# Drive_21_04_33.net
KiCad netlist of a schematic drawn in Altium Designer
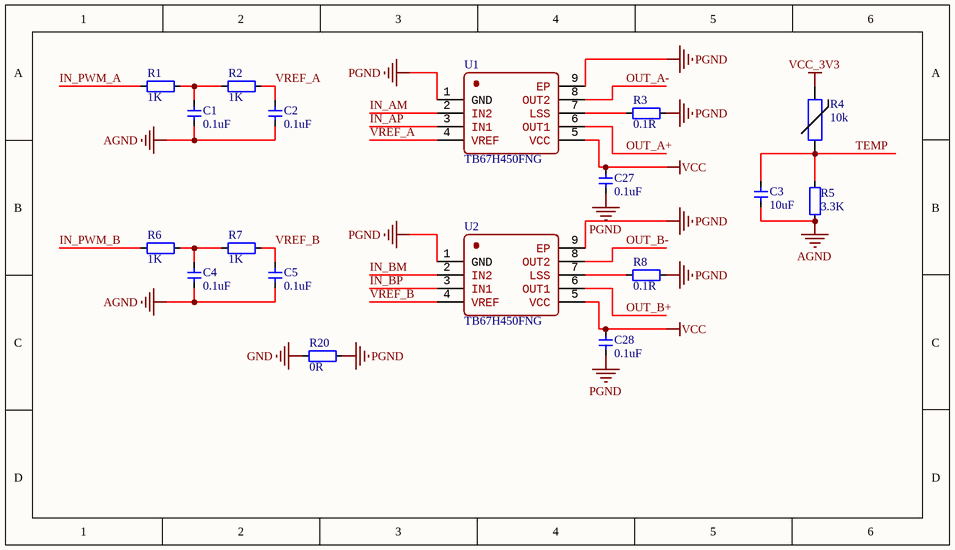
[diagram p0: Drive 21.04.33.SchDoc]

(export (version "E")
  (design (tool "Eeschema 10.0.6"))
  (components
    (comp (ref "C1")
      (value "0.1uF")
      (footprint "motor42-lib:CAP_0402")
      (description "Capacitor")
      (libsource (lib "MyPcbLib") (part "电容-0402"))
    )
    (comp (ref "C2")
      (value "0.1uF")
      (footprint "motor42-lib:CAP_0402")
      (description "Capacitor")
      (libsource (lib "MyPcbLib") (part "电容-0402"))
    )
    (comp (ref "C3")
      (value "10uF")
      (footprint "CAP_0402")
      (description "Capacitor")
      (libsource (lib "MyPcbLib") (part "电容-0402"))
    )
    (comp (ref "C4")
      (value "0.1uF")
      (footprint "motor42-lib:CAP_0402")
      (description "Capacitor")
      (libsource (lib "MyPcbLib") (part "电容-0402"))
    )
    (comp (ref "C5")
      (value "0.1uF")
      (footprint "motor42-lib:CAP_0402")
      (description "Capacitor")
      (libsource (lib "MyPcbLib") (part "电容-0402"))
    )
    (comp (ref "C27")
      (value "0.1uF")
      (footprint "motor42-lib:CAP_0402")
      (description "Capacitor")
      (libsource (lib "MyPcbLib") (part "电容-0402"))
    )
    (comp (ref "C28")
      (value "0.1uF")
      (footprint "motor42-lib:CAP_0402")
      (description "Capacitor")
      (libsource (lib "MyPcbLib") (part "电容-0402"))
    )
    (comp (ref "R1")
      (value "1K")
      (footprint "RES_0402")
      (description "Resistor")
      (libsource (lib "MyPcbLib") (part "电阻-0402"))
    )
    (comp (ref "R2")
      (value "1K")
      (footprint "RES_0402")
      (description "Resistor")
      (libsource (lib "MyPcbLib") (part "电阻-0402"))
    )
    (comp (ref "R3")
      (value "0.1R")
      (footprint "1206-RES")
      (description "Resistor")
      (libsource (lib "MyPcbLib") (part "电阻-1206"))
    )
    (comp (ref "R4")
      (value "10k")
      (footprint "RES_0402")
      (description "THERMISTOR 10K OHM NTC 0402 SMD")
      (fields (field (name "Comment") "NCP15XH103F03RC"))
      (libsource (lib "MyPcbLib") (part "NCP15XH103F03RC"))
    )
    (comp (ref "R5")
      (value "3.3K")
      (footprint "RES_0402")
      (description "Resistor")
      (libsource (lib "") (part "电阻-0402_1"))
    )
    (comp (ref "R6")
      (value "1K")
      (footprint "RES_0402")
      (description "Resistor")
      (libsource (lib "MyPcbLib") (part "电阻-0402"))
    )
    (comp (ref "R7")
      (value "1K")
      (footprint "RES_0402")
      (description "Resistor")
      (libsource (lib "MyPcbLib") (part "电阻-0402"))
    )
    (comp (ref "R8")
      (value "0.1R")
      (footprint "1206-RES")
      (description "Resistor")
      (libsource (lib "MyPcbLib") (part "电阻-1206"))
    )
    (comp (ref "R20")
      (value "0R")
      (footprint "1206-RES")
      (description "Resistor")
      (libsource (lib "MyPcbLib") (part "电阻-1206"))
    )
    (comp (ref "U1")
      (value "TB67H450FNG")
      (footprint "SO-8-PAD")
      (description "PWM Chopper Type DC Brushed Motor Driver")
      (libsource (lib "MyPcbLib") (part "TB67H450FNG"))
    )
    (comp (ref "U2")
      (value "TB67H450FNG")
      (footprint "SO-8-PAD")
      (description "PWM Chopper Type DC Brushed Motor Driver")
      (libsource (lib "MyPcbLib") (part "TB67H450FNG"))
    )
  )
  (nets
    (net (code "1") (name "/IN_AM") (class "Default")
      (node (ref "U1") (pin "2") (pinfunction "IN2_2") (pintype "passive"))
    )
    (net (code "2") (name "/IN_AP") (class "Default")
      (node (ref "U1") (pin "3") (pinfunction "IN1_3") (pintype "passive"))
    )
    (net (code "3") (name "/IN_BM") (class "Default")
      (node (ref "U2") (pin "2") (pinfunction "IN2_2") (pintype "passive"))
    )
    (net (code "4") (name "/IN_BP") (class "Default")
      (node (ref "U2") (pin "3") (pinfunction "IN1_3") (pintype "passive"))
    )
    (net (code "5") (name "/IN_PWM_A") (class "Default")
      (node (ref "R1") (pin "1") (pinfunction "1_1") (pintype "passive"))
    )
    (net (code "6") (name "/IN_PWM_B") (class "Default")
      (node (ref "R6") (pin "1") (pinfunction "1_1") (pintype "passive"))
    )
    (net (code "7") (name "/OUT_A+") (class "Default")
      (node (ref "U1") (pin "6") (pinfunction "OUT1_6") (pintype "passive"))
    )
    (net (code "8") (name "/OUT_A-") (class "Default")
      (node (ref "U1") (pin "8") (pinfunction "OUT2_8") (pintype "passive"))
    )
    (net (code "9") (name "/OUT_B+") (class "Default")
      (node (ref "U2") (pin "6") (pinfunction "OUT1_6") (pintype "passive"))
    )
    (net (code "10") (name "/OUT_B-") (class "Default")
      (node (ref "U2") (pin "8") (pinfunction "OUT2_8") (pintype "passive"))
    )
    (net (code "11") (name "/TEMP") (class "Default")
      (node (ref "C3") (pin "2") (pinfunction "2_2") (pintype "passive"))
      (node (ref "R4") (pin "1") (pinfunction "0_1") (pintype "passive"))
      (node (ref "R5") (pin "2") (pinfunction "2_2") (pintype "passive"))
    )
    (net (code "12") (name "/VREF_A") (class "Default")
      (node (ref "C2") (pin "2") (pinfunction "2_2") (pintype "passive"))
      (node (ref "R2") (pin "2") (pinfunction "2_2") (pintype "passive"))
      (node (ref "U1") (pin "4") (pinfunction "VREF_4") (pintype "passive"))
    )
    (net (code "13") (name "/VREF_B") (class "Default")
      (node (ref "C5") (pin "2") (pinfunction "2_2") (pintype "passive"))
      (node (ref "R7") (pin "2") (pinfunction "2_2") (pintype "passive"))
      (node (ref "U2") (pin "4") (pinfunction "VREF_4") (pintype "passive"))
    )
    (net (code "14") (name "AGND") (class "Default")
      (node (ref "C1") (pin "1") (pinfunction "1_1") (pintype "passive"))
      (node (ref "C2") (pin "1") (pinfunction "1_1") (pintype "passive"))
      (node (ref "C3") (pin "1") (pinfunction "1_1") (pintype "passive"))
      (node (ref "C4") (pin "1") (pinfunction "1_1") (pintype "passive"))
      (node (ref "C5") (pin "1") (pinfunction "1_1") (pintype "passive"))
      (node (ref "R5") (pin "1") (pinfunction "1_1") (pintype "passive"))
    )
    (net (code "15") (name "GND") (class "Default")
      (node (ref "R20") (pin "1") (pinfunction "1_1") (pintype "passive"))
    )
    (net (code "16") (name "Net-(C1-Pad2)") (class "Default")
      (node (ref "C1") (pin "2") (pinfunction "2_2") (pintype "passive"))
      (node (ref "R1") (pin "2") (pinfunction "2_2") (pintype "passive"))
      (node (ref "R2") (pin "1") (pinfunction "1_1") (pintype "passive"))
    )
    (net (code "17") (name "Net-(C4-Pad2)") (class "Default")
      (node (ref "C4") (pin "2") (pinfunction "2_2") (pintype "passive"))
      (node (ref "R6") (pin "2") (pinfunction "2_2") (pintype "passive"))
      (node (ref "R7") (pin "1") (pinfunction "1_1") (pintype "passive"))
    )
    (net (code "18") (name "Net-(U1-LSS)") (class "Default")
      (node (ref "R3") (pin "1") (pinfunction "1_1") (pintype "passive"))
      (node (ref "U1") (pin "7") (pinfunction "LSS_7") (pintype "passive"))
    )
    (net (code "19") (name "Net-(U2-LSS)") (class "Default")
      (node (ref "R8") (pin "1") (pinfunction "1_1") (pintype "passive"))
      (node (ref "U2") (pin "7") (pinfunction "LSS_7") (pintype "passive"))
    )
    (net (code "20") (name "PGND") (class "Default")
      (node (ref "C27") (pin "1") (pinfunction "1_1") (pintype "passive"))
      (node (ref "C28") (pin "1") (pinfunction "1_1") (pintype "passive"))
      (node (ref "R20") (pin "2") (pinfunction "2_2") (pintype "passive"))
      (node (ref "R3") (pin "2") (pinfunction "2_2") (pintype "passive"))
      (node (ref "R8") (pin "2") (pinfunction "2_2") (pintype "passive"))
      (node (ref "U1") (pin "1") (pinfunction "GND_1") (pintype "passive"))
      (node (ref "U1") (pin "9") (pinfunction "EP_9") (pintype "passive"))
      (node (ref "U2") (pin "1") (pinfunction "GND_1") (pintype "passive"))
      (node (ref "U2") (pin "9") (pinfunction "EP_9") (pintype "passive"))
    )
    (net (code "21") (name "VCC") (class "Default")
      (node (ref "C27") (pin "2") (pinfunction "2_2") (pintype "passive"))
      (node (ref "C28") (pin "2") (pinfunction "2_2") (pintype "passive"))
      (node (ref "U1") (pin "5") (pinfunction "VCC_5") (pintype "passive"))
      (node (ref "U2") (pin "5") (pinfunction "VCC_5") (pintype "passive"))
    )
    (net (code "22") (name "VCC_3V3") (class "Default")
      (node (ref "R4") (pin "2") (pinfunction "0_2") (pintype "passive"))
    )
  )
)
